# control-interface.net
KiCad netlist of a schematic drawn in Altium Designer
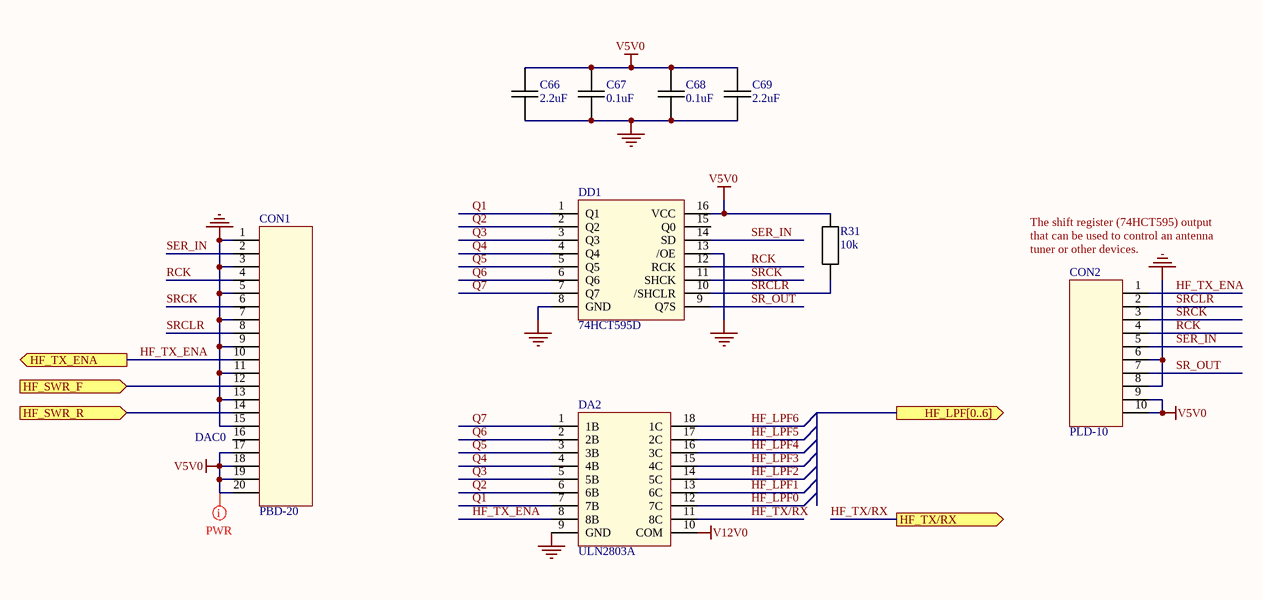
[diagram p0: control-interface.SchDoc]

(export (version "E")
  (design (tool "Eeschema 10.0.6"))
  (components
    (comp (ref "C66")
      (value "2.2uF")
      (footprint "CAPC2013X100N")
      (description "Capacitor 2x1.25 mm")
      (libsource (lib "common-lib") (part "Cap0805"))
    )
    (comp (ref "C67")
      (value "0.1uF")
      (footprint "CAPC2013X100N")
      (description "Capacitor 2x1.25 mm")
      (libsource (lib "common-lib") (part "Cap0805"))
    )
    (comp (ref "C68")
      (value "0.1uF")
      (footprint "CAPC2013X100N")
      (description "Capacitor 2x1.25 mm")
      (libsource (lib "common-lib") (part "Cap0805"))
    )
    (comp (ref "C69")
      (value "2.2uF")
      (footprint "CAPC2013X100N")
      (description "Capacitor 2x1.25 mm")
      (libsource (lib "common-lib") (part "Cap0805"))
    )
    (comp (ref "CON1")
      (value "PBD-20")
      (footprint "PBD-20")
      (libsource (lib "common-lib") (part "CONNECTOR-20"))
    )
    (comp (ref "CON2") (value "PLD-10") (footprint "PLD-10") (libsource (lib "PALib") (part "CONNECTOR-10")))
    (comp (ref "DA2")
      (value "ULN2803A")
      (footprint "SOIC127P1030X265-18N")
      (description "Darlington Transistor Array")
      (libsource (lib "PALib") (part "ULN2803A"))
    )
    (comp (ref "DD1")
      (value "74HCT595D")
      (footprint "SOIC127P600X175-16N")
      (description "8-bit serial-in, serial or parallel-out shift register with output\r\nlatches; 3-state,\r\nimrad")
      (libsource (lib "PALib") (part "74HCT595D"))
    )
    (comp (ref "R31")
      (value "10k")
      (footprint "RESC2013X64N")
      (libsource (lib "common-lib") (part "Res0805"))
    )
  )
  (nets
    (net (code "1") (name "/HF_LPF0") (class "Default")
      (node (ref "DA2") (pin "12") (pinfunction "7C_12") (pintype "passive"))
    )
    (net (code "2") (name "/HF_LPF1") (class "Default")
      (node (ref "DA2") (pin "13") (pinfunction "6C_13") (pintype "passive"))
    )
    (net (code "3") (name "/HF_LPF2") (class "Default")
      (node (ref "DA2") (pin "14") (pinfunction "5C_14") (pintype "passive"))
    )
    (net (code "4") (name "/HF_LPF3") (class "Default")
      (node (ref "DA2") (pin "15") (pinfunction "4C_15") (pintype "passive"))
    )
    (net (code "5") (name "/HF_LPF4") (class "Default")
      (node (ref "DA2") (pin "16") (pinfunction "3C_16") (pintype "passive"))
    )
    (net (code "6") (name "/HF_LPF5") (class "Default")
      (node (ref "DA2") (pin "17") (pinfunction "2C_17") (pintype "passive"))
    )
    (net (code "7") (name "/HF_LPF6") (class "Default")
      (node (ref "DA2") (pin "18") (pinfunction "1C_18") (pintype "passive"))
    )
    (net (code "9") (name "/HF_SWR_F") (class "Default")
      (node (ref "CON1") (pin "12") (pinfunction "12_12") (pintype "passive"))
    )
    (net (code "10") (name "/HF_SWR_R") (class "Default")
      (node (ref "CON1") (pin "14") (pinfunction "14_14") (pintype "passive"))
    )
    (net (code "11") (name "/HF_TX_ENA") (class "Default")
      (node (ref "CON1") (pin "10") (pinfunction "10_10") (pintype "passive"))
      (node (ref "CON2") (pin "1") (pinfunction "1_1") (pintype "passive"))
      (node (ref "DA2") (pin "8") (pinfunction "8B_8") (pintype "passive"))
    )
    (net (code "12") (name "/HF_TX{slash}RX") (class "Default")
      (node (ref "DA2") (pin "11") (pinfunction "8C_11") (pintype "passive"))
    )
    (net (code "13") (name "/Q1") (class "Default")
      (node (ref "DA2") (pin "7") (pinfunction "7B_7") (pintype "passive"))
      (node (ref "DD1") (pin "1") (pinfunction "Q1_1") (pintype "passive"))
    )
    (net (code "14") (name "/Q2") (class "Default")
      (node (ref "DA2") (pin "6") (pinfunction "6B_6") (pintype "passive"))
      (node (ref "DD1") (pin "2") (pinfunction "Q2_2") (pintype "passive"))
    )
    (net (code "15") (name "/Q3") (class "Default")
      (node (ref "DA2") (pin "5") (pinfunction "5B_5") (pintype "passive"))
      (node (ref "DD1") (pin "3") (pinfunction "Q3_3") (pintype "passive"))
    )
    (net (code "16") (name "/Q4") (class "Default")
      (node (ref "DA2") (pin "4") (pinfunction "4B_4") (pintype "passive"))
      (node (ref "DD1") (pin "4") (pinfunction "Q4_4") (pintype "passive"))
    )
    (net (code "17") (name "/Q5") (class "Default")
      (node (ref "DA2") (pin "3") (pinfunction "3B_3") (pintype "passive"))
      (node (ref "DD1") (pin "5") (pinfunction "Q5_5") (pintype "passive"))
    )
    (net (code "18") (name "/Q6") (class "Default")
      (node (ref "DA2") (pin "2") (pinfunction "2B_2") (pintype "passive"))
      (node (ref "DD1") (pin "6") (pinfunction "Q6_6") (pintype "passive"))
    )
    (net (code "19") (name "/Q7") (class "Default")
      (node (ref "DA2") (pin "1") (pinfunction "1B_1") (pintype "passive"))
      (node (ref "DD1") (pin "7") (pinfunction "Q7_7") (pintype "passive"))
    )
    (net (code "20") (name "/RCK") (class "Default")
      (node (ref "CON1") (pin "4") (pinfunction "4_4") (pintype "passive"))
      (node (ref "CON2") (pin "4") (pinfunction "4_4") (pintype "passive"))
      (node (ref "DD1") (pin "12") (pinfunction "RCK_12") (pintype "passive"))
    )
    (net (code "21") (name "/SER_IN") (class "Default")
      (node (ref "CON1") (pin "2") (pinfunction "2_2") (pintype "passive"))
      (node (ref "CON2") (pin "5") (pinfunction "5_5") (pintype "passive"))
      (node (ref "DD1") (pin "14") (pinfunction "SD_14") (pintype "passive"))
    )
    (net (code "22") (name "/SRCK") (class "Default")
      (node (ref "CON1") (pin "6") (pinfunction "6_6") (pintype "passive"))
      (node (ref "CON2") (pin "3") (pinfunction "3_3") (pintype "passive"))
      (node (ref "DD1") (pin "11") (pinfunction "SHCK_11") (pintype "passive"))
    )
    (net (code "23") (name "/SRCLR") (class "Default")
      (node (ref "CON1") (pin "8") (pinfunction "8_8") (pintype "passive"))
      (node (ref "CON2") (pin "2") (pinfunction "2_2") (pintype "passive"))
      (node (ref "DD1") (pin "10") (pinfunction "/SHCLR_10") (pintype "passive"))
      (node (ref "R31") (pin "1") (pintype "passive"))
    )
    (net (code "24") (name "/SR_OUT") (class "Default")
      (node (ref "CON2") (pin "7") (pinfunction "7_7") (pintype "passive"))
      (node (ref "DD1") (pin "9") (pinfunction "Q7S_9") (pintype "passive"))
    )
    (net (code "25") (name "GND") (class "Default")
      (node (ref "C66") (pin "1") (pintype "passive"))
      (node (ref "C67") (pin "1") (pintype "passive"))
      (node (ref "C68") (pin "1") (pintype "passive"))
      (node (ref "C69") (pin "1") (pintype "passive"))
      (node (ref "CON1") (pin "1") (pinfunction "1_1") (pintype "passive"))
      (node (ref "CON1") (pin "11") (pinfunction "11_11") (pintype "passive"))
      (node (ref "CON1") (pin "13") (pinfunction "13_13") (pintype "passive"))
      (node (ref "CON1") (pin "15") (pinfunction "15_15") (pintype "passive"))
      (node (ref "CON1") (pin "3") (pinfunction "3_3") (pintype "passive"))
      (node (ref "CON1") (pin "5") (pinfunction "5_5") (pintype "passive"))
      (node (ref "CON1") (pin "7") (pinfunction "7_7") (pintype "passive"))
      (node (ref "CON1") (pin "9") (pinfunction "9_9") (pintype "passive"))
      (node (ref "CON2") (pin "6") (pinfunction "6_6") (pintype "passive"))
      (node (ref "CON2") (pin "8") (pinfunction "8_8") (pintype "passive"))
      (node (ref "DA2") (pin "9") (pinfunction "GND_9") (pintype "passive"))
      (node (ref "DD1") (pin "13") (pinfunction "/OE_13") (pintype "passive"))
      (node (ref "DD1") (pin "8") (pinfunction "GND_8") (pintype "passive"))
    )
    (net (code "26") (name "V5V0") (class "Default")
      (node (ref "C66") (pin "2") (pintype "passive"))
      (node (ref "C67") (pin "2") (pintype "passive"))
      (node (ref "C68") (pin "2") (pintype "passive"))
      (node (ref "C69") (pin "2") (pintype "passive"))
      (node (ref "CON1") (pin "17") (pinfunction "17_17") (pintype "passive"))
      (node (ref "CON1") (pin "18") (pinfunction "18_18") (pintype "passive"))
      (node (ref "CON1") (pin "19") (pinfunction "19_19") (pintype "passive"))
      (node (ref "CON1") (pin "20") (pinfunction "20_20") (pintype "passive"))
      (node (ref "CON2") (pin "10") (pinfunction "10_10") (pintype "passive"))
      (node (ref "CON2") (pin "9") (pinfunction "9_9") (pintype "passive"))
      (node (ref "DD1") (pin "16") (pinfunction "VCC_16") (pintype "passive"))
      (node (ref "R31") (pin "2") (pintype "passive"))
    )
    (net (code "27") (name "V12V0") (class "Default")
      (node (ref "DA2") (pin "10") (pinfunction "COM_10") (pintype "passive"))
    )
    (net (code "28") (name "unconnected-(CON1-Pad16)") (class "Default")
      (node (ref "CON1") (pin "16") (pinfunction "16_16") (pintype "passive"))
    )
    (net (code "29") (name "unconnected-(DD1-Q0-Pad15)") (class "Default")
      (node (ref "DD1") (pin "15") (pinfunction "Q0_15") (pintype "passive"))
    )
  )
)
